# RS422.net
KiCad netlist of a schematic drawn in Altium Designer
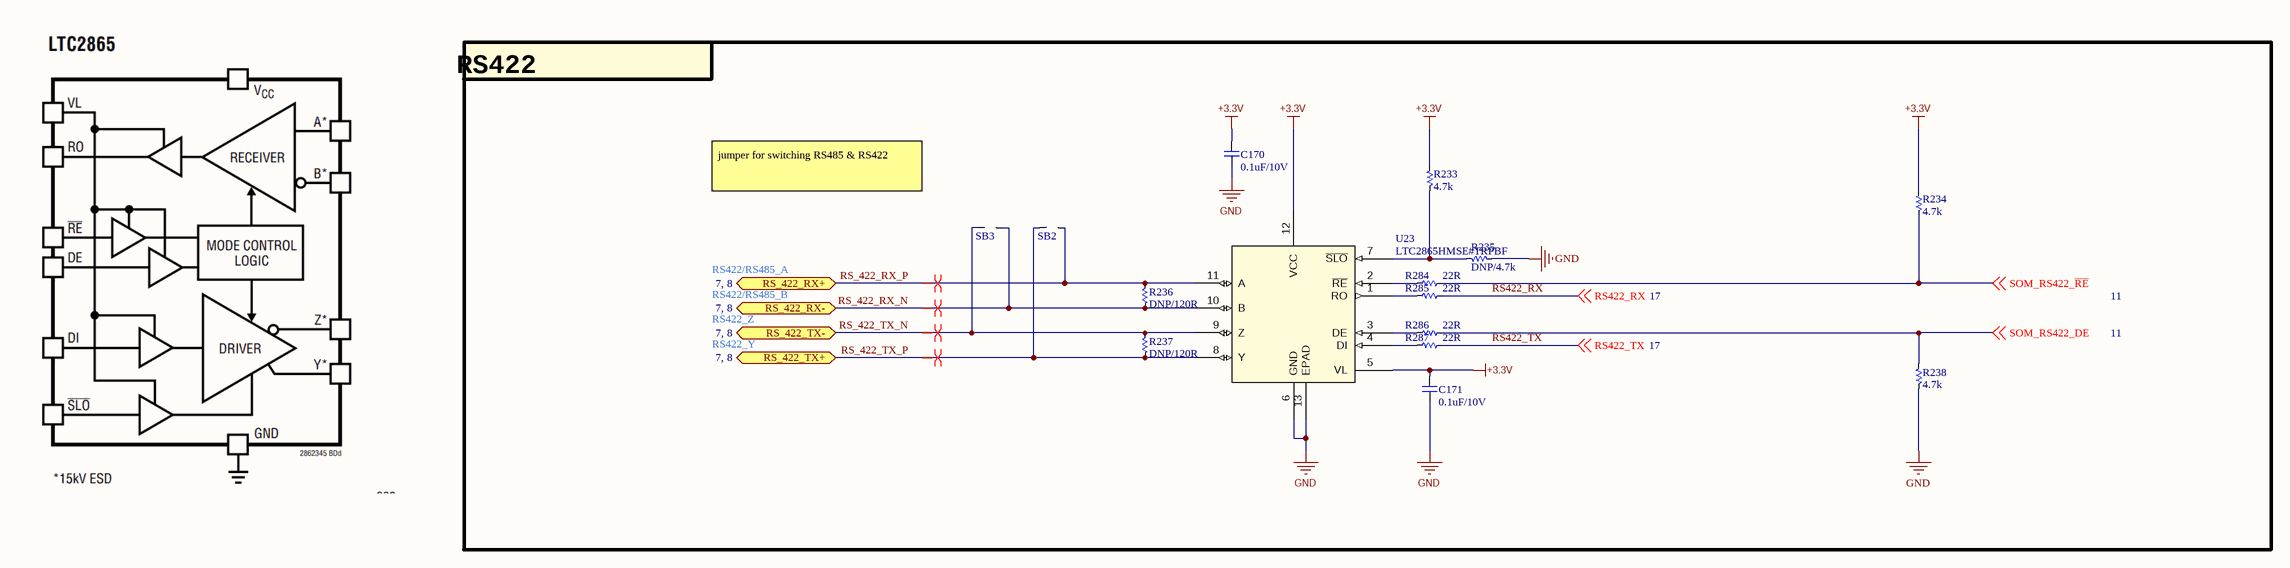
[diagram p0: RS422.SchDoc]

(export (version "E")
  (design (tool "Eeschema 10.0.6"))
  (components
    (comp (ref "C170")
      (value "0.1uF/10V")
      (footprint "CAP_C_1005X50_L")
      (description "CAP")
      (libsource (lib "LABLIB") (part "_CAP_C_2"))
    )
    (comp (ref "C171")
      (value "0.1uF/10V")
      (footprint "CAP_C_1005X50_L")
      (description "CAP")
      (libsource (lib "LABLIB") (part "_CAP_C_2"))
    )
    (comp (ref "R233")
      (value "4.7k")
      (footprint "RES_C_1005x30_L")
      (description "RES")
      (libsource (lib "IFBschelib") (part "_RES_B_2"))
    )
    (comp (ref "R234")
      (value "4.7k")
      (footprint "RES_C_1005x30_L")
      (description "RES")
      (libsource (lib "IFBschelib") (part "_RES_B_2"))
    )
    (comp (ref "R235")
      (value "DNP/4.7k")
      (footprint "RES_C_1005x30_L")
      (description "RES")
      (libsource (lib "IFBschelib") (part "_RES_B_2"))
    )
    (comp (ref "R236")
      (value "DNP/120R")
      (footprint "RES_C_1005x30_L")
      (description "RES")
      (libsource (lib "IFBschelib") (part "_RES_B_2"))
    )
    (comp (ref "R237")
      (value "DNP/120R")
      (footprint "RES_C_1005x30_L")
      (description "RES")
      (libsource (lib "IFBschelib") (part "_RES_B_2"))
    )
    (comp (ref "R238")
      (value "4.7k")
      (footprint "RES_C_1005x30_L")
      (description "RES")
      (libsource (lib "IFBschelib") (part "_RES_B_2"))
    )
    (comp (ref "R284")
      (value "22R")
      (footprint "RES_C_1005x30_L")
      (description "RES")
      (libsource (lib "LABLIB") (part "_RES_B_2"))
    )
    (comp (ref "R285")
      (value "22R")
      (footprint "RES_C_1005x30_L")
      (description "RES")
      (libsource (lib "LABLIB") (part "_RES_B_2"))
    )
    (comp (ref "R286")
      (value "22R")
      (footprint "RES_C_1005x30_L")
      (description "RES")
      (libsource (lib "LABLIB") (part "_RES_B_2"))
    )
    (comp (ref "R287")
      (value "22R")
      (footprint "RES_C_1005x30_L")
      (description "RES")
      (libsource (lib "LABLIB") (part "_RES_B_2"))
    )
    (comp (ref "SB2")
      (value "JUMPER")
      (footprint "JUMPER_1608")
      (libsource (lib "IFBschelib") (part "JUMPER"))
    )
    (comp (ref "SB3")
      (value "JUMPER")
      (footprint "JUMPER_1608")
      (libsource (lib "IFBschelib") (part "JUMPER"))
    )
    (comp (ref "U23")
      (value "LTC2865HMSE#TRPBF")
      (footprint "MSOP-12_MSE_LIT")
      (description "Â±60V Fault Protected 3V to 5.5V RS485/RS422 Transceivers")
      (fields (field (name "COPYRIGHT") "Copyright (C) 2025 Ultra Librarian. All rights reserved."))
      (libsource (lib "IFBschelib") (part "LTC2865HMSETRPBF"))
    )
  )
  (nets
    (net (code "1") (name "+3.3V") (class "Default")
      (node (ref "C170") (pin "2") (pinfunction "2_2") (pintype "passive"))
      (node (ref "C171") (pin "2") (pinfunction "2_2") (pintype "passive"))
      (node (ref "R233") (pin "2") (pinfunction "2_2") (pintype "passive"))
      (node (ref "R234") (pin "2") (pinfunction "2_2") (pintype "passive"))
      (node (ref "U23") (pin "12") (pinfunction "VCC_12") (pintype "power_in"))
      (node (ref "U23") (pin "5") (pinfunction "VL_5") (pintype "power_in"))
    )
    (net (code "2") (name "/RS_422_RX_N") (class "Default")
      (node (ref "R236") (pin "2") (pinfunction "2_2") (pintype "passive"))
      (node (ref "SB3") (pin "1") (pinfunction "1_1") (pintype "passive"))
      (node (ref "U23") (pin "10") (pinfunction "B_10") (pintype "bidirectional"))
    )
    (net (code "3") (name "/RS_422_RX_P") (class "Default")
      (node (ref "R236") (pin "1") (pinfunction "1_1") (pintype "passive"))
      (node (ref "SB2") (pin "1") (pinfunction "1_1") (pintype "passive"))
      (node (ref "U23") (pin "11") (pinfunction "A_11") (pintype "bidirectional"))
    )
    (net (code "4") (name "/RS_422_TX_N") (class "Default")
      (node (ref "R237") (pin "1") (pinfunction "1_1") (pintype "passive"))
      (node (ref "SB3") (pin "2") (pinfunction "2_2") (pintype "passive"))
      (node (ref "U23") (pin "9") (pinfunction "Z_9") (pintype "bidirectional"))
    )
    (net (code "5") (name "/RS_422_TX_P") (class "Default")
      (node (ref "R237") (pin "2") (pinfunction "2_2") (pintype "passive"))
      (node (ref "SB2") (pin "2") (pinfunction "2_2") (pintype "passive"))
      (node (ref "U23") (pin "8") (pinfunction "Y_8") (pintype "bidirectional"))
    )
    (net (code "6") (name "GND") (class "Default")
      (node (ref "C170") (pin "1") (pinfunction "1_1") (pintype "passive"))
      (node (ref "C171") (pin "1") (pinfunction "1_1") (pintype "passive"))
      (node (ref "R235") (pin "2") (pinfunction "2_2") (pintype "passive"))
      (node (ref "R238") (pin "1") (pinfunction "1_1") (pintype "passive"))
      (node (ref "U23") (pin "13") (pinfunction "EPAD_13") (pintype "passive"))
      (node (ref "U23") (pin "6") (pinfunction "GND_6") (pintype "power_in"))
    )
    (net (code "7") (name "Net-(U23-DE)") (class "Default")
      (node (ref "R286") (pin "1") (pinfunction "1_1") (pintype "passive"))
      (node (ref "U23") (pin "3") (pinfunction "DE_3") (pintype "input"))
    )
    (net (code "8") (name "Net-(U23-DI)") (class "Default")
      (node (ref "R287") (pin "1") (pinfunction "1_1") (pintype "passive"))
      (node (ref "U23") (pin "4") (pinfunction "DI_4") (pintype "input"))
    )
    (net (code "9") (name "Net-(U23-RO)") (class "Default")
      (node (ref "R285") (pin "1") (pinfunction "1_1") (pintype "passive"))
      (node (ref "U23") (pin "1") (pinfunction "RO_1") (pintype "output"))
    )
    (net (code "10") (name "Net-(U23-~{RE})") (class "Default")
      (node (ref "R284") (pin "1") (pinfunction "1_1") (pintype "passive"))
      (node (ref "U23") (pin "2") (pinfunction "~{RE}_2") (pintype "input"))
    )
    (net (code "11") (name "Net-(U23-~{SLO})") (class "Default")
      (node (ref "R233") (pin "1") (pinfunction "1_1") (pintype "passive"))
      (node (ref "R235") (pin "1") (pinfunction "1_1") (pintype "passive"))
      (node (ref "U23") (pin "7") (pinfunction "~{SLO}_7") (pintype "input"))
    )
    (net (code "12") (name "RS422_RX") (class "Default")
      (node (ref "R285") (pin "2") (pinfunction "2_2") (pintype "passive"))
    )
    (net (code "13") (name "RS422_TX") (class "Default")
      (node (ref "R287") (pin "2") (pinfunction "2_2") (pintype "passive"))
    )
    (net (code "14") (name "SOM_RS422_DE") (class "Default")
      (node (ref "R238") (pin "2") (pinfunction "2_2") (pintype "passive"))
      (node (ref "R286") (pin "2") (pinfunction "2_2") (pintype "passive"))
    )
    (net (code "15") (name "SOM_RS422_~{RE}") (class "Default")
      (node (ref "R234") (pin "1") (pinfunction "1_1") (pintype "passive"))
      (node (ref "R284") (pin "2") (pinfunction "2_2") (pintype "passive"))
    )
  )
)
